# untitled.net
KiCad netlist of a schematic drawn in EAGLE
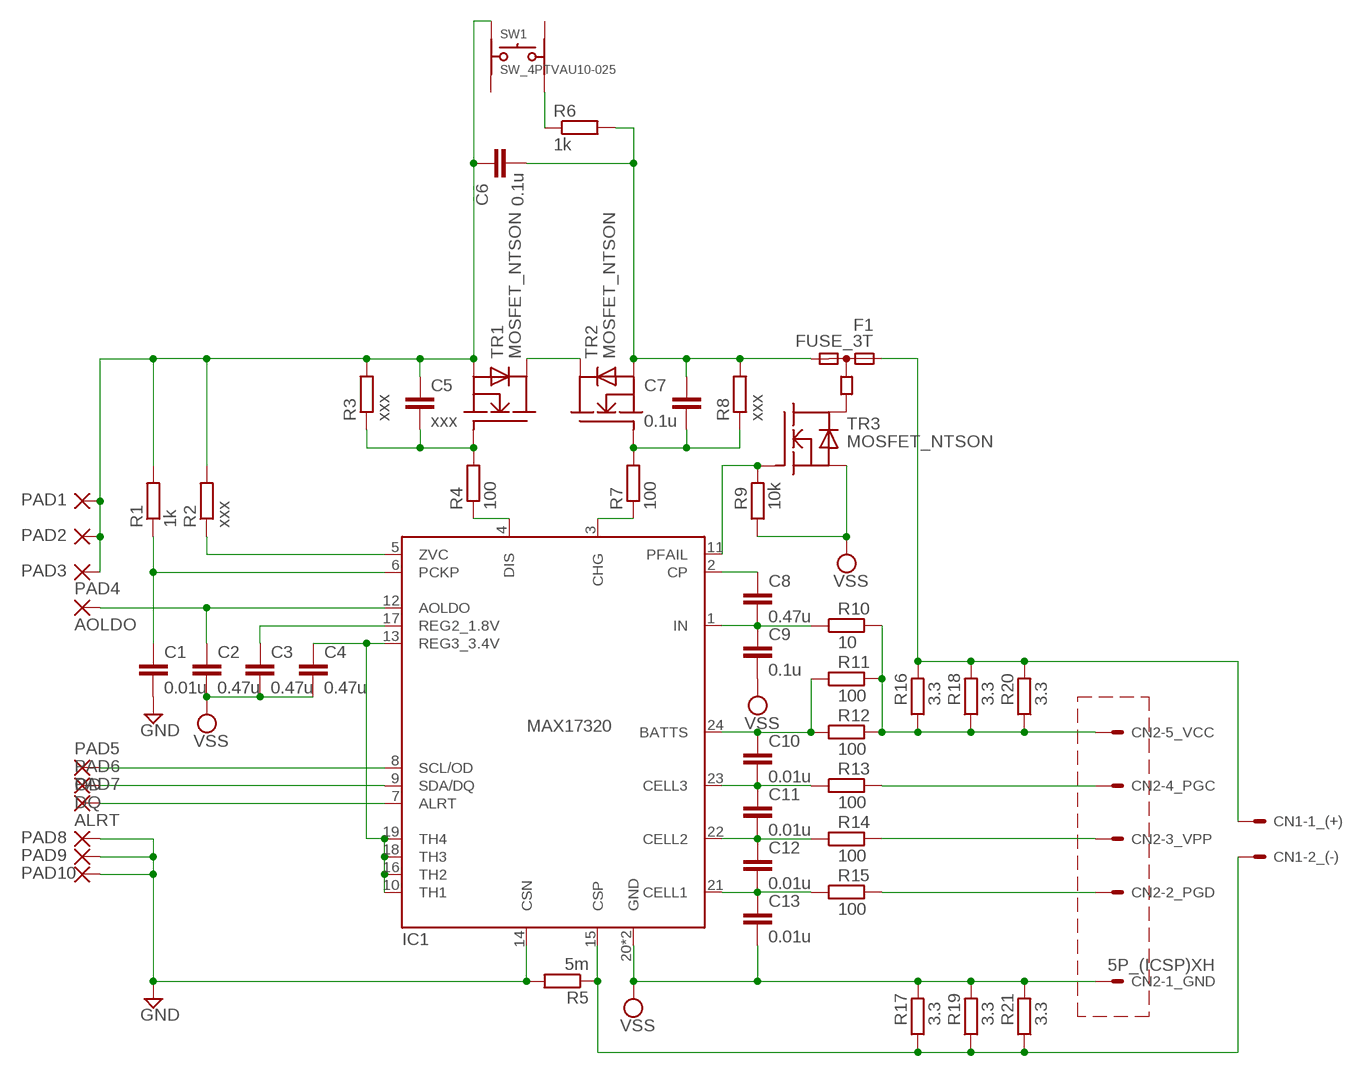
[diagram p0: schematic, sheet 1]

(export (version "E")
  (design (tool "Eeschema 10.0.6"))
  (components
    (comp (ref "C1")
      (value "0.01u")
      (footprint "eagle-import:C0402")
      (libsource (lib "eagle-import") (part "C-EUC0402"))
    )
    (comp (ref "C2")
      (value "0.47u")
      (footprint "eagle-import:C0402")
      (libsource (lib "eagle-import") (part "C-EUC0402"))
    )
    (comp (ref "C3")
      (value "0.47u")
      (footprint "eagle-import:C0402")
      (libsource (lib "eagle-import") (part "C-EUC0402"))
    )
    (comp (ref "C4")
      (value "0.47u")
      (footprint "eagle-import:C0402")
      (libsource (lib "eagle-import") (part "C-EUC0402"))
    )
    (comp (ref "C5")
      (value "xxx")
      (footprint "eagle-import:C0402")
      (libsource (lib "eagle-import") (part "C-EUC0402"))
    )
    (comp (ref "C6")
      (value "0.1u")
      (footprint "eagle-import:C0402")
      (libsource (lib "eagle-import") (part "C-EUC0402"))
    )
    (comp (ref "C7")
      (value "0.1u")
      (footprint "eagle-import:C0402")
      (libsource (lib "eagle-import") (part "C-EUC0402"))
    )
    (comp (ref "C8")
      (value "0.47u")
      (footprint "eagle-import:C0402")
      (libsource (lib "eagle-import") (part "C-EUC0402"))
    )
    (comp (ref "C9")
      (value "0.1u")
      (footprint "eagle-import:C0402")
      (libsource (lib "eagle-import") (part "C-EUC0402"))
    )
    (comp (ref "C10")
      (value "0.01u")
      (footprint "eagle-import:C0402")
      (libsource (lib "eagle-import") (part "C-EUC0402"))
    )
    (comp (ref "C11")
      (value "0.01u")
      (footprint "eagle-import:C0402")
      (libsource (lib "eagle-import") (part "C-EUC0402"))
    )
    (comp (ref "C12")
      (value "0.01u")
      (footprint "eagle-import:C0402")
      (libsource (lib "eagle-import") (part "C-EUC0402"))
    )
    (comp (ref "C13")
      (value "0.01u")
      (footprint "eagle-import:C0402")
      (libsource (lib "eagle-import") (part "C-EUC0402"))
    )
    (comp (ref "CN1")
      (value "2P_(POWER)VH")
      (footprint "eagle-import:VH-2")
      (libsource (lib "eagle-import") (part "2P_(POWER)VH"))
    )
    (comp (ref "CN2")
      (value "5P_(ICSP)XH")
      (footprint "eagle-import:XH-5")
      (libsource (lib "eagle-import") (part "5P_(ICSP)XH"))
    )
    (comp (ref "F1")
      (value "FUSE_3T")
      (footprint "eagle-import:FUSE_ITV4030")
      (libsource (lib "eagle-import") (part "FUSE_3T"))
    )
    (comp (ref "IC1")
      (value "MAX17320")
      (footprint "eagle-import:TQFN24-EP")
      (libsource (lib "eagle-import") (part "MAX17320"))
    )
    (comp (ref "PAD1")
      (value "WIREPAD2.0/1.2")
      (footprint "eagle-import:2.0_1.3")
      (libsource (lib "eagle-import") (part "WIREPAD2.0/1.2"))
    )
    (comp (ref "PAD2")
      (value "WIREPAD2.0/1.2")
      (footprint "eagle-import:2.0_1.3")
      (libsource (lib "eagle-import") (part "WIREPAD2.0/1.2"))
    )
    (comp (ref "PAD3")
      (value "WIREPAD2.0/1.2")
      (footprint "eagle-import:2.0_1.3")
      (libsource (lib "eagle-import") (part "WIREPAD2.0/1.2"))
    )
    (comp (ref "PAD4")
      (value "AOLDO")
      (footprint "eagle-import:2.0_1.3")
      (libsource (lib "eagle-import") (part "WIREPAD2.0/1.2"))
    )
    (comp (ref "PAD5")
      (value "OD")
      (footprint "eagle-import:2.0_1.3")
      (libsource (lib "eagle-import") (part "WIREPAD2.0/1.2"))
    )
    (comp (ref "PAD6")
      (value "DQ")
      (footprint "eagle-import:2.0_1.3")
      (libsource (lib "eagle-import") (part "WIREPAD2.0/1.2"))
    )
    (comp (ref "PAD7")
      (value "ALRT")
      (footprint "eagle-import:2.0_1.3")
      (libsource (lib "eagle-import") (part "WIREPAD2.0/1.2"))
    )
    (comp (ref "PAD8")
      (value "WIREPAD2.0/1.2")
      (footprint "eagle-import:2.0_1.3")
      (libsource (lib "eagle-import") (part "WIREPAD2.0/1.2"))
    )
    (comp (ref "PAD9")
      (value "WIREPAD2.0/1.2")
      (footprint "eagle-import:2.0_1.3")
      (libsource (lib "eagle-import") (part "WIREPAD2.0/1.2"))
    )
    (comp (ref "PAD10")
      (value "WIREPAD2.0/1.2")
      (footprint "eagle-import:2.0_1.3")
      (libsource (lib "eagle-import") (part "WIREPAD2.0/1.2"))
    )
    (comp (ref "R1")
      (value "1k")
      (footprint "eagle-import:R0402")
      (libsource (lib "eagle-import") (part "R-EU_R0402"))
    )
    (comp (ref "R2")
      (value "xxx")
      (footprint "eagle-import:R0402")
      (libsource (lib "eagle-import") (part "R-EU_R0402"))
    )
    (comp (ref "R3")
      (value "xxx")
      (footprint "eagle-import:R0402")
      (libsource (lib "eagle-import") (part "R-EU_R0402"))
    )
    (comp (ref "R4")
      (value "100")
      (footprint "eagle-import:R0402")
      (libsource (lib "eagle-import") (part "R-EU_R0402"))
    )
    (comp (ref "R5")
      (value "5m")
      (footprint "eagle-import:R1210")
      (libsource (lib "eagle-import") (part "R-EU_R1210"))
    )
    (comp (ref "R6")
      (value "1k")
      (footprint "eagle-import:R0402")
      (libsource (lib "eagle-import") (part "R-EU_R0402"))
    )
    (comp (ref "R7")
      (value "100")
      (footprint "eagle-import:R0402")
      (libsource (lib "eagle-import") (part "R-EU_R0402"))
    )
    (comp (ref "R8")
      (value "xxx")
      (footprint "eagle-import:R0402")
      (libsource (lib "eagle-import") (part "R-EU_R0402"))
    )
    (comp (ref "R9")
      (value "10k")
      (footprint "eagle-import:R0402")
      (libsource (lib "eagle-import") (part "R-EU_R0402"))
    )
    (comp (ref "R10")
      (value "10")
      (footprint "eagle-import:R0402")
      (libsource (lib "eagle-import") (part "R-EU_R0402"))
    )
    (comp (ref "R11")
      (value "100")
      (footprint "eagle-import:R0402")
      (libsource (lib "eagle-import") (part "R-EU_R0402"))
    )
    (comp (ref "R12")
      (value "100")
      (footprint "eagle-import:R0402")
      (libsource (lib "eagle-import") (part "R-EU_R0402"))
    )
    (comp (ref "R13")
      (value "100")
      (footprint "eagle-import:R0402")
      (libsource (lib "eagle-import") (part "R-EU_R0402"))
    )
    (comp (ref "R14")
      (value "100")
      (footprint "eagle-import:R0402")
      (libsource (lib "eagle-import") (part "R-EU_R0402"))
    )
    (comp (ref "R15")
      (value "100")
      (footprint "eagle-import:R0402")
      (libsource (lib "eagle-import") (part "R-EU_R0402"))
    )
    (comp (ref "R16")
      (value "3.3")
      (footprint "eagle-import:R0402")
      (libsource (lib "eagle-import") (part "R-EU_R0402"))
    )
    (comp (ref "R17")
      (value "3.3")
      (footprint "eagle-import:R0402")
      (libsource (lib "eagle-import") (part "R-EU_R0402"))
    )
    (comp (ref "R18")
      (value "3.3")
      (footprint "eagle-import:R0402")
      (libsource (lib "eagle-import") (part "R-EU_R0402"))
    )
    (comp (ref "R19")
      (value "3.3")
      (footprint "eagle-import:R0402")
      (libsource (lib "eagle-import") (part "R-EU_R0402"))
    )
    (comp (ref "R20")
      (value "3.3")
      (footprint "eagle-import:R0402")
      (libsource (lib "eagle-import") (part "R-EU_R0402"))
    )
    (comp (ref "R21")
      (value "3.3")
      (footprint "eagle-import:R0402")
      (libsource (lib "eagle-import") (part "R-EU_R0402"))
    )
    (comp (ref "SW1")
      (value "SW_4PTVAU10-025")
      (footprint "eagle-import:TVAU10-025")
      (libsource (lib "eagle-import") (part "SW_4PTVAU10-025"))
    )
    (comp (ref "TR1")
      (value "MOSFET_NTSON")
      (footprint "eagle-import:TSON_ADVANCE")
      (libsource (lib "eagle-import") (part "MOSFET_NTSON"))
    )
    (comp (ref "TR2")
      (value "MOSFET_NTSON")
      (footprint "eagle-import:TSON_ADVANCE")
      (libsource (lib "eagle-import") (part "MOSFET_NTSON"))
    )
    (comp (ref "TR3")
      (value "MOSFET_NTSON")
      (footprint "eagle-import:TSON_ADVANCE")
      (libsource (lib "eagle-import") (part "MOSFET_NTSON"))
    )
  )
  (nets
    (net (code "1") (name "GND") (class "Default")
      (node (ref "C1") (pin "2") (pinfunction "2_2") (pintype "passive"))
      (node (ref "IC1") (pin "14") (pinfunction "CSN_14") (pintype "input"))
      (node (ref "PAD10") (pin "1") (pinfunction "P_1") (pintype "passive"))
      (node (ref "PAD8") (pin "1") (pinfunction "P_1") (pintype "passive"))
      (node (ref "PAD9") (pin "1") (pinfunction "P_1") (pintype "passive"))
      (node (ref "R5") (pin "2") (pinfunction "2_2") (pintype "passive"))
    )
    (net (code "2") (name "Net-(C6-Pad2)") (class "Default")
      (node (ref "C6") (pin "2") (pinfunction "2_2") (pintype "passive"))
      (node (ref "C7") (pin "1") (pinfunction "1_1") (pintype "passive"))
      (node (ref "F1") (pin "F2") (pinfunction "F2_F2") (pintype "passive"))
      (node (ref "R6") (pin "2") (pinfunction "2_2") (pintype "passive"))
      (node (ref "R8") (pin "2") (pinfunction "2_2") (pintype "passive"))
      (node (ref "TR2") (pin "1") (pinfunction "S_1") (pintype "bidirectional"))
      (node (ref "TR2") (pin "2") (pinfunction "S_2") (pintype "bidirectional"))
      (node (ref "TR2") (pin "3") (pinfunction "S_3") (pintype "bidirectional"))
    )
    (net (code "3") (name "Net-(CN1A-S)") (class "Default")
      (node (ref "CN1") (pin "1") (pinfunction "S_1") (pintype "passive"))
      (node (ref "F1") (pin "F1") (pinfunction "F1_F1") (pintype "passive"))
      (node (ref "R16") (pin "2") (pinfunction "2_2") (pintype "passive"))
      (node (ref "R18") (pin "2") (pinfunction "2_2") (pintype "passive"))
      (node (ref "R20") (pin "2") (pinfunction "2_2") (pintype "passive"))
    )
    (net (code "4") (name "Net-(CN1B-S)") (class "Default")
      (node (ref "CN1") (pin "2") (pinfunction "S_2") (pintype "passive"))
      (node (ref "IC1") (pin "15") (pinfunction "CSP_15") (pintype "input"))
      (node (ref "R17") (pin "1") (pinfunction "1_1") (pintype "passive"))
      (node (ref "R19") (pin "1") (pinfunction "1_1") (pintype "passive"))
      (node (ref "R21") (pin "1") (pinfunction "1_1") (pintype "passive"))
      (node (ref "R5") (pin "1") (pinfunction "1_1") (pintype "passive"))
    )
    (net (code "5") (name "Net-(CN2B-S)") (class "Default")
      (node (ref "CN2") (pin "4") (pinfunction "S_4") (pintype "passive"))
      (node (ref "R15") (pin "2") (pinfunction "2_2") (pintype "passive"))
    )
    (net (code "6") (name "Net-(CN2C-S)") (class "Default")
      (node (ref "CN2") (pin "3") (pinfunction "S_3") (pintype "passive"))
      (node (ref "R14") (pin "2") (pinfunction "2_2") (pintype "passive"))
    )
    (net (code "7") (name "Net-(CN2D-S)") (class "Default")
      (node (ref "CN2") (pin "2") (pinfunction "S_2") (pintype "passive"))
      (node (ref "R13") (pin "2") (pinfunction "2_2") (pintype "passive"))
    )
    (net (code "8") (name "Net-(CN2E-S)") (class "Default")
      (node (ref "CN2") (pin "1") (pinfunction "S_1") (pintype "passive"))
      (node (ref "R10") (pin "2") (pinfunction "2_2") (pintype "passive"))
      (node (ref "R11") (pin "2") (pinfunction "2_2") (pintype "passive"))
      (node (ref "R12") (pin "2") (pinfunction "2_2") (pintype "passive"))
      (node (ref "R16") (pin "1") (pinfunction "1_1") (pintype "passive"))
      (node (ref "R18") (pin "1") (pinfunction "1_1") (pintype "passive"))
      (node (ref "R20") (pin "1") (pinfunction "1_1") (pintype "passive"))
    )
    (net (code "9") (name "Net-(F1-PadH)") (class "Default")
      (node (ref "F1") (pin "H") (pinfunction "H_H") (pintype "passive"))
      (node (ref "TR3") (pin "5") (pinfunction "D_5") (pintype "bidirectional"))
      (node (ref "TR3") (pin "5_") (pinfunction "D_5_") (pintype "bidirectional"))
      (node (ref "TR3") (pin "6") (pinfunction "D_6") (pintype "bidirectional"))
      (node (ref "TR3") (pin "7") (pinfunction "D_7") (pintype "bidirectional"))
      (node (ref "TR3") (pin "8") (pinfunction "D_8") (pintype "bidirectional"))
      (node (ref "TR3") (pin "8_") (pinfunction "D_8_") (pintype "bidirectional"))
      (node (ref "TR3") (pin "EP") (pinfunction "D_EP") (pintype "bidirectional"))
      (node (ref "TR3") (pin "EP2") (pinfunction "D_EP2") (pintype "bidirectional"))
    )
    (net (code "10") (name "Net-(IC1-ALRT)") (class "Default")
      (node (ref "IC1") (pin "7") (pinfunction "ALRT_7") (pintype "output"))
      (node (ref "PAD7") (pin "1") (pinfunction "P_1") (pintype "passive"))
    )
    (net (code "11") (name "Net-(IC1-AOLDO)") (class "Default")
      (node (ref "C2") (pin "1") (pinfunction "1_1") (pintype "passive"))
      (node (ref "IC1") (pin "12") (pinfunction "AOLDO_12") (pintype "output"))
      (node (ref "PAD4") (pin "1") (pinfunction "P_1") (pintype "passive"))
    )
    (net (code "12") (name "Net-(IC1-BATTS)") (class "Default")
      (node (ref "C10") (pin "1") (pinfunction "1_1") (pintype "passive"))
      (node (ref "IC1") (pin "24") (pinfunction "BATTS_24") (pintype "input"))
      (node (ref "R11") (pin "1") (pinfunction "1_1") (pintype "passive"))
      (node (ref "R12") (pin "1") (pinfunction "1_1") (pintype "passive"))
    )
    (net (code "13") (name "Net-(IC1-CELL1)") (class "Default")
      (node (ref "C12") (pin "2") (pinfunction "2_2") (pintype "passive"))
      (node (ref "C13") (pin "1") (pinfunction "1_1") (pintype "passive"))
      (node (ref "IC1") (pin "21") (pinfunction "CELL1_21") (pintype "input"))
      (node (ref "R15") (pin "1") (pinfunction "1_1") (pintype "passive"))
    )
    (net (code "14") (name "Net-(IC1-CELL2)") (class "Default")
      (node (ref "C11") (pin "2") (pinfunction "2_2") (pintype "passive"))
      (node (ref "C12") (pin "1") (pinfunction "1_1") (pintype "passive"))
      (node (ref "IC1") (pin "22") (pinfunction "CELL2_22") (pintype "input"))
      (node (ref "R14") (pin "1") (pinfunction "1_1") (pintype "passive"))
    )
    (net (code "15") (name "Net-(IC1-CELL3)") (class "Default")
      (node (ref "C10") (pin "2") (pinfunction "2_2") (pintype "passive"))
      (node (ref "C11") (pin "1") (pinfunction "1_1") (pintype "passive"))
      (node (ref "IC1") (pin "23") (pinfunction "CELL3_23") (pintype "input"))
      (node (ref "R13") (pin "1") (pinfunction "1_1") (pintype "passive"))
    )
    (net (code "16") (name "Net-(IC1-CHG)") (class "Default")
      (node (ref "IC1") (pin "3") (pinfunction "CHG_3") (pintype "output"))
      (node (ref "R7") (pin "1") (pinfunction "1_1") (pintype "passive"))
    )
    (net (code "17") (name "Net-(IC1-CP)") (class "Default")
      (node (ref "C8") (pin "1") (pinfunction "1_1") (pintype "passive"))
      (node (ref "IC1") (pin "2") (pinfunction "CP_2") (pintype "input"))
    )
    (net (code "18") (name "Net-(IC1-DIS)") (class "Default")
      (node (ref "IC1") (pin "4") (pinfunction "DIS_4") (pintype "output"))
      (node (ref "R4") (pin "1") (pinfunction "1_1") (pintype "passive"))
    )
    (net (code "19") (name "Net-(IC1-IN)") (class "Default")
      (node (ref "C8") (pin "2") (pinfunction "2_2") (pintype "passive"))
      (node (ref "C9") (pin "1") (pinfunction "1_1") (pintype "passive"))
      (node (ref "IC1") (pin "1") (pinfunction "IN_1") (pintype "input"))
      (node (ref "R10") (pin "1") (pinfunction "1_1") (pintype "passive"))
    )
    (net (code "20") (name "Net-(IC1-PCKP)") (class "Default")
      (node (ref "C1") (pin "1") (pinfunction "1_1") (pintype "passive"))
      (node (ref "IC1") (pin "6") (pinfunction "PCKP_6") (pintype "input"))
      (node (ref "R1") (pin "1") (pinfunction "1_1") (pintype "passive"))
    )
    (net (code "21") (name "Net-(IC1-PFAIL)") (class "Default")
      (node (ref "IC1") (pin "11") (pinfunction "PFAIL_11") (pintype "output"))
      (node (ref "R9") (pin "2") (pinfunction "2_2") (pintype "passive"))
      (node (ref "TR3") (pin "4") (pinfunction "G_4") (pintype "bidirectional"))
    )
    (net (code "22") (name "Net-(IC1-REG2_1.8V)") (class "Default")
      (node (ref "C3") (pin "1") (pinfunction "1_1") (pintype "passive"))
      (node (ref "IC1") (pin "17") (pinfunction "REG2_1.8V_17") (pintype "output"))
    )
    (net (code "23") (name "Net-(IC1-REG3_3.4V)") (class "Default")
      (node (ref "C4") (pin "1") (pinfunction "1_1") (pintype "passive"))
      (node (ref "IC1") (pin "10") (pinfunction "TH1_10") (pintype "input"))
      (node (ref "IC1") (pin "13") (pinfunction "REG3_3.4V_13") (pintype "output"))
      (node (ref "IC1") (pin "16") (pinfunction "TH2_16") (pintype "input"))
      (node (ref "IC1") (pin "18") (pinfunction "TH3_18") (pintype "input"))
      (node (ref "IC1") (pin "19") (pinfunction "TH4_19") (pintype "input"))
    )
    (net (code "24") (name "Net-(IC1-SCL{slash}OD)") (class "Default")
      (node (ref "IC1") (pin "8") (pinfunction "SCL/OD_8") (pintype "bidirectional"))
      (node (ref "PAD5") (pin "1") (pinfunction "P_1") (pintype "passive"))
    )
    (net (code "25") (name "Net-(IC1-SDA{slash}DQ)") (class "Default")
      (node (ref "IC1") (pin "9") (pinfunction "SDA/DQ_9") (pintype "bidirectional"))
      (node (ref "PAD6") (pin "1") (pinfunction "P_1") (pintype "passive"))
    )
    (net (code "26") (name "Net-(IC1-ZVC)") (class "Default")
      (node (ref "IC1") (pin "5") (pinfunction "ZVC_5") (pintype "power_in"))
      (node (ref "R2") (pin "1") (pinfunction "1_1") (pintype "passive"))
    )
    (net (code "27") (name "Net-(PAD1-P)") (class "Default")
      (node (ref "C5") (pin "1") (pinfunction "1_1") (pintype "passive"))
      (node (ref "C6") (pin "1") (pinfunction "1_1") (pintype "passive"))
      (node (ref "PAD1") (pin "1") (pinfunction "P_1") (pintype "passive"))
      (node (ref "PAD2") (pin "1") (pinfunction "P_1") (pintype "passive"))
      (node (ref "PAD3") (pin "1") (pinfunction "P_1") (pintype "passive"))
      (node (ref "R1") (pin "2") (pinfunction "2_2") (pintype "passive"))
      (node (ref "R2") (pin "2") (pinfunction "2_2") (pintype "passive"))
      (node (ref "R3") (pin "2") (pinfunction "2_2") (pintype "passive"))
      (node (ref "SW1") (pin "P$1") (pinfunction "A_P$1") (pintype "bidirectional"))
      (node (ref "TR1") (pin "1") (pinfunction "S_1") (pintype "bidirectional"))
      (node (ref "TR1") (pin "2") (pinfunction "S_2") (pintype "bidirectional"))
      (node (ref "TR1") (pin "3") (pinfunction "S_3") (pintype "bidirectional"))
    )
    (net (code "28") (name "Net-(SW1-=B)") (class "Default")
      (node (ref "R6") (pin "1") (pinfunction "1_1") (pintype "passive"))
      (node (ref "SW1") (pin "P$4") (pinfunction "=B_P$4") (pintype "bidirectional"))
    )
    (net (code "29") (name "Net-(TR1-D-Pad5)") (class "Default")
      (node (ref "TR1") (pin "5") (pinfunction "D_5") (pintype "bidirectional"))
      (node (ref "TR1") (pin "5_") (pinfunction "D_5_") (pintype "bidirectional"))
      (node (ref "TR1") (pin "6") (pinfunction "D_6") (pintype "bidirectional"))
      (node (ref "TR1") (pin "7") (pinfunction "D_7") (pintype "bidirectional"))
      (node (ref "TR1") (pin "8") (pinfunction "D_8") (pintype "bidirectional"))
      (node (ref "TR1") (pin "8_") (pinfunction "D_8_") (pintype "bidirectional"))
      (node (ref "TR1") (pin "EP") (pinfunction "D_EP") (pintype "bidirectional"))
      (node (ref "TR1") (pin "EP2") (pinfunction "D_EP2") (pintype "bidirectional"))
      (node (ref "TR2") (pin "5") (pinfunction "D_5") (pintype "bidirectional"))
      (node (ref "TR2") (pin "5_") (pinfunction "D_5_") (pintype "bidirectional"))
      (node (ref "TR2") (pin "6") (pinfunction "D_6") (pintype "bidirectional"))
      (node (ref "TR2") (pin "7") (pinfunction "D_7") (pintype "bidirectional"))
      (node (ref "TR2") (pin "8") (pinfunction "D_8") (pintype "bidirectional"))
      (node (ref "TR2") (pin "8_") (pinfunction "D_8_") (pintype "bidirectional"))
      (node (ref "TR2") (pin "EP") (pinfunction "D_EP") (pintype "bidirectional"))
      (node (ref "TR2") (pin "EP2") (pinfunction "D_EP2") (pintype "bidirectional"))
    )
    (net (code "30") (name "Net-(TR1-G)") (class "Default")
      (node (ref "C5") (pin "2") (pinfunction "2_2") (pintype "passive"))
      (node (ref "R3") (pin "1") (pinfunction "1_1") (pintype "passive"))
      (node (ref "R4") (pin "2") (pinfunction "2_2") (pintype "passive"))
      (node (ref "TR1") (pin "4") (pinfunction "G_4") (pintype "bidirectional"))
    )
    (net (code "31") (name "Net-(TR2-G)") (class "Default")
      (node (ref "C7") (pin "2") (pinfunction "2_2") (pintype "passive"))
      (node (ref "R7") (pin "2") (pinfunction "2_2") (pintype "passive"))
      (node (ref "R8") (pin "1") (pinfunction "1_1") (pintype "passive"))
      (node (ref "TR2") (pin "4") (pinfunction "G_4") (pintype "bidirectional"))
    )
    (net (code "32") (name "VSS") (class "Default")
      (node (ref "C13") (pin "2") (pinfunction "2_2") (pintype "passive"))
      (node (ref "C2") (pin "2") (pinfunction "2_2") (pintype "passive"))
      (node (ref "C3") (pin "2") (pinfunction "2_2") (pintype "passive"))
      (node (ref "C4") (pin "2") (pinfunction "2_2") (pintype "passive"))
      (node (ref "C9") (pin "2") (pinfunction "2_2") (pintype "passive"))
      (node (ref "CN2") (pin "5") (pinfunction "S_5") (pintype "passive"))
      (node (ref "IC1") (pin "20") (pinfunction "GND_20") (pintype "power_in"))
      (node (ref "IC1") (pin "EXP") (pinfunction "GND_EXP") (pintype "power_in"))
      (node (ref "R17") (pin "2") (pinfunction "2_2") (pintype "passive"))
      (node (ref "R19") (pin "2") (pinfunction "2_2") (pintype "passive"))
      (node (ref "R21") (pin "2") (pinfunction "2_2") (pintype "passive"))
      (node (ref "R9") (pin "1") (pinfunction "1_1") (pintype "passive"))
      (node (ref "TR3") (pin "1") (pinfunction "S_1") (pintype "bidirectional"))
      (node (ref "TR3") (pin "2") (pinfunction "S_2") (pintype "bidirectional"))
      (node (ref "TR3") (pin "3") (pinfunction "S_3") (pintype "bidirectional"))
    )
    (net (code "33") (name "unconnected-(SW1-=A-PadP$2)") (class "Default")
      (node (ref "SW1") (pin "P$2") (pinfunction "=A_P$2") (pintype "bidirectional"))
    )
    (net (code "34") (name "unconnected-(SW1-B-PadP$3)") (class "Default")
      (node (ref "SW1") (pin "P$3") (pinfunction "B_P$3") (pintype "bidirectional"))
    )
  )
)
